# UBC-Thunderbots_PCB_Power__archive_power.net
KiCad netlist of a schematic drawn in Altium Designer
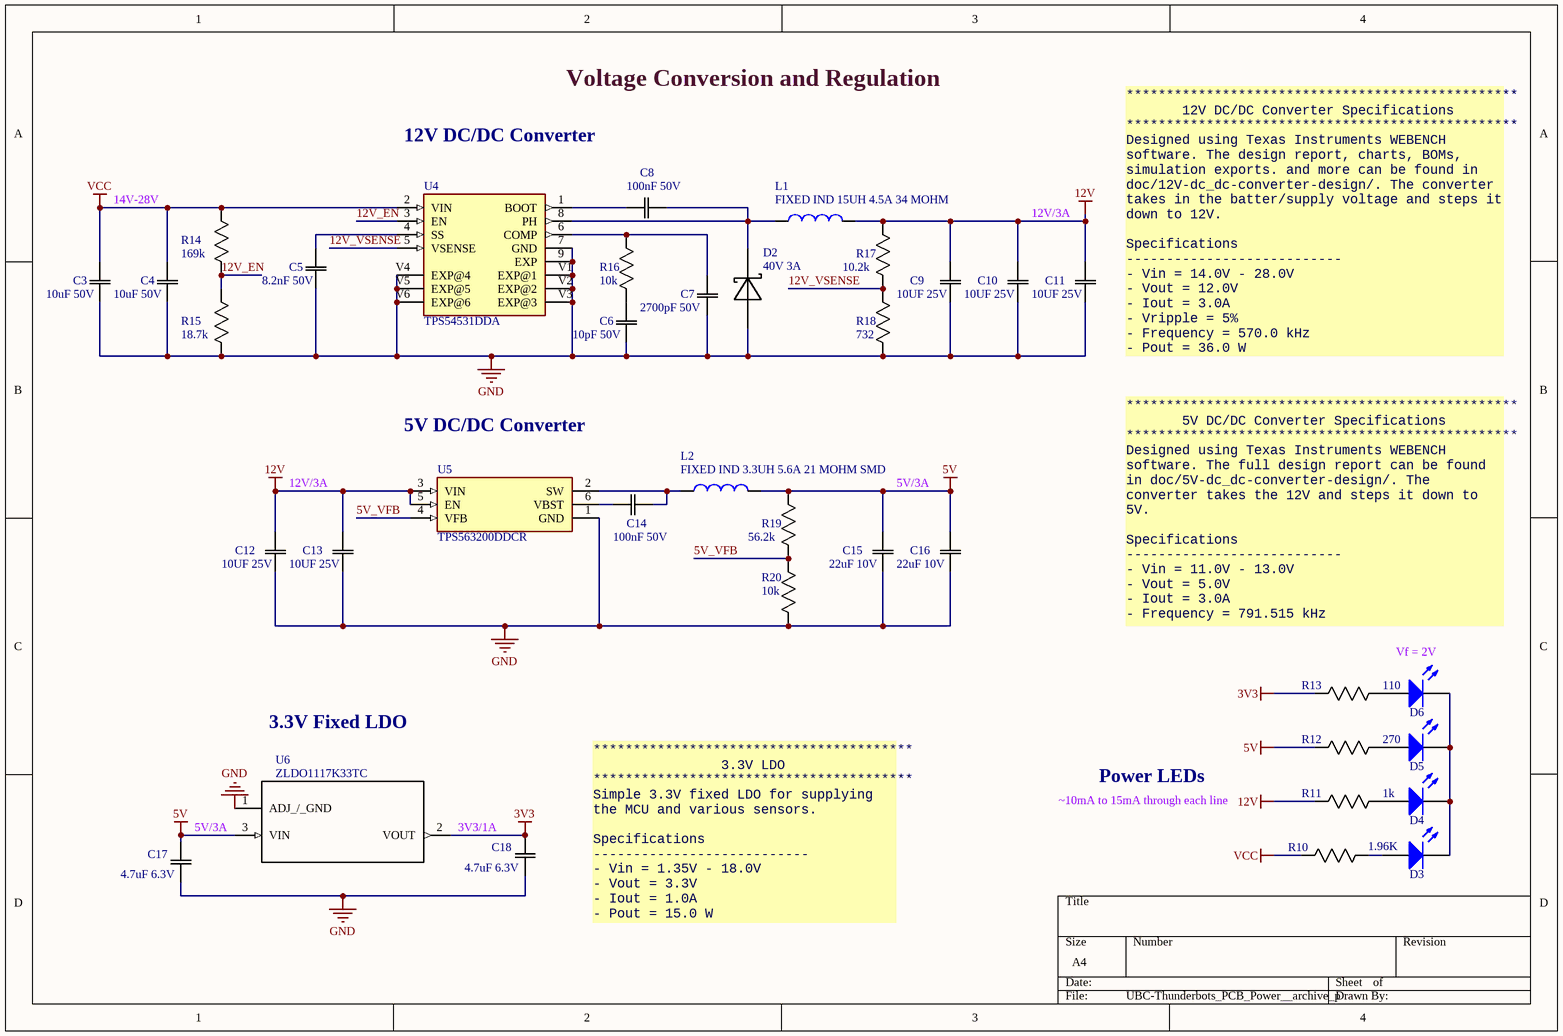
[diagram p0: UBC-Thunderbots_PCB_Power__archive_power-v2.2_pcb__regulation.SchDoc]

(export (version "E")
  (design (tool "Eeschema 10.0.6"))
  (components
    (comp (ref "C3")
      (value "10uF 50V")
      (footprint "1210")
      (description "CAP CER 10UF 50V X7R")
      (fields (field (name "TOLERANCE") "10%"))
      (libsource (lib "AltiumLibraries") (part "CAP 10uF 50V"))
    )
    (comp (ref "C4")
      (value "10uF 50V")
      (footprint "1210")
      (description "CAP CER 10UF 50V X7R")
      (fields (field (name "TOLERANCE") "10%"))
      (libsource (lib "AltiumLibraries") (part "CAP 10uF 50V"))
    )
    (comp (ref "C5")
      (value "8.2nF 50V")
      (footprint "0805")
      (description "CAP CER 8200PF 50V X7R 0805")
      (fields (field (name "TOLERANCE") "10%"))
      (libsource (lib "AltiumLibraries") (part "CAP 8.2nF 50V"))
    )
    (comp (ref "C6")
      (value "10pF 50V")
      (footprint "0603")
      (description "CAP CER 10PF 50V X7R 0603")
      (fields (field (name "TOLERANCE") "10%"))
      (libsource (lib "AltiumLibraries") (part "CAP 10pF 50V"))
    )
    (comp (ref "C7")
      (value "2700pF 50V")
      (footprint "0805")
      (description "CAP CER 2700PF 50V X7R 0805")
      (fields (field (name "TOLERANCE") "10%"))
      (libsource (lib "AltiumLibraries") (part "CAP 2700pF 50V"))
    )
    (comp (ref "C8")
      (value "100nF 50V")
      (footprint "0805")
      (description "CAP CER 0.1UF 50V X7R 0805")
      (fields (field (name "TOLERANCE") "10%"))
      (libsource (lib "AltiumLibraries") (part "CAP 100nF 50V"))
    )
    (comp (ref "C9")
      (value "10UF 25V")
      (footprint "1206")
      (description "CAP CER 10UF 25V X5R 1206")
      (fields (field (name "TOLERANCE") "10%"))
      (libsource (lib "AltiumLibraries") (part "CAP 10uF 25V"))
    )
    (comp (ref "C10")
      (value "10UF 25V")
      (footprint "1206")
      (description "CAP CER 10UF 25V X5R 1206")
      (fields (field (name "TOLERANCE") "10%"))
      (libsource (lib "AltiumLibraries") (part "CAP 10uF 25V"))
    )
    (comp (ref "C11")
      (value "10UF 25V")
      (footprint "1206")
      (description "CAP CER 10UF 25V X5R 1206")
      (fields (field (name "TOLERANCE") "10%"))
      (libsource (lib "AltiumLibraries") (part "CAP 10uF 25V"))
    )
    (comp (ref "C12")
      (value "10UF 25V")
      (footprint "1206")
      (description "CAP CER 10UF 25V X5R 1206")
      (fields (field (name "TOLERANCE") "10%"))
      (libsource (lib "AltiumLibraries") (part "CAP 10uF 25V"))
    )
    (comp (ref "C13")
      (value "10UF 25V")
      (footprint "1206")
      (description "CAP CER 10UF 25V X5R 1206")
      (fields (field (name "TOLERANCE") "10%"))
      (libsource (lib "AltiumLibraries") (part "CAP 10uF 25V"))
    )
    (comp (ref "C14")
      (value "100nF 50V")
      (footprint "0805")
      (description "CAP CER 0.1UF 50V X7R 0805")
      (fields (field (name "TOLERANCE") "10%"))
      (libsource (lib "AltiumLibraries") (part "CAP 100nF 50V"))
    )
    (comp (ref "C15")
      (value "22uF 10V")
      (footprint "0805")
      (description "CAP CER 2.2UF 10V X5R 0805")
      (fields (field (name "TOLERANCE") "20%"))
      (libsource (lib "AltiumLibraries") (part "CAP 22uF 10V"))
    )
    (comp (ref "C16")
      (value "22uF 10V")
      (footprint "0805")
      (description "CAP CER 2.2UF 10V X5R 0805")
      (fields (field (name "TOLERANCE") "20%"))
      (libsource (lib "AltiumLibraries") (part "CAP 22uF 10V"))
    )
    (comp (ref "C17")
      (value "4.7uF 6.3V")
      (footprint "0805")
      (description "CAP CER 4.7UF 6.3V X5R 0805")
      (fields (field (name "TOLERANCE") "10%"))
      (libsource (lib "AltiumLibraries") (part "CAP 4.7uF 6.3V"))
    )
    (comp (ref "C18")
      (value "4.7uF 6.3V")
      (footprint "0805")
      (description "CAP CER 4.7UF 6.3V X5R 0805")
      (fields (field (name "TOLERANCE") "10%"))
      (libsource (lib "AltiumLibraries") (part "CAP 4.7uF 6.3V"))
    )
    (comp (ref "D2")
      (value "40V 3A")
      (footprint "DO-214AC")
      (description "Diode Schottky 40V 3A Surface Mount SMA")
      (libsource (lib "AltiumLibraries") (part "DIODE SCHOTTKY 40V 3A"))
    )
    (comp (ref "D3")
      (value "LED2")
      (footprint "3.2X1.6X1.1")
      (description "Typical RED, GREEN, YELLOW, AMBER GaAs LED")
      (libsource (lib "AltiumLibraries") (part "LED GREEN SMD"))
    )
    (comp (ref "D4")
      (value "LED2")
      (footprint "3.2X1.6X1.1")
      (description "Typical RED, GREEN, YELLOW, AMBER GaAs LED")
      (libsource (lib "AltiumLibraries") (part "LED GREEN SMD"))
    )
    (comp (ref "D5")
      (value "LED2")
      (footprint "3.2X1.6X1.1")
      (description "Typical RED, GREEN, YELLOW, AMBER GaAs LED")
      (libsource (lib "AltiumLibraries") (part "LED GREEN SMD"))
    )
    (comp (ref "D6")
      (value "LED2")
      (footprint "3.2X1.6X1.1")
      (description "Typical RED, GREEN, YELLOW, AMBER GaAs LED")
      (libsource (lib "AltiumLibraries") (part "LED GREEN SMD"))
    )
    (comp (ref "L1")
      (value "FIXED IND 15UH 4.5A 34 MOHM")
      (description "15µH Unshielded Wirewound Inductor 4.5A 34mOhm Max Nonstandard")
      (fields (field (name "MP") "SDR1307-150ML") (field (name "MF") "Bourns Inc."))
      (libsource (lib "AltiumLibraries") (part "SDR1307-150ML"))
    )
    (comp (ref "L2")
      (value "FIXED IND 3.3UH 5.6A 21 MOHM SMD")
      (description "3.3µH Semi-Shielded Wirewound Inductor 5.6A 21mOhm Max Nonstandard")
      (fields (field (name "MP") "SRN8040-3R3Y") (field (name "MF") "Bourns Inc."))
      (libsource (lib "AltiumLibraries") (part "SRN8040-3R3Y"))
    )
    (comp (ref "R10")
      (value "1.96K")
      (footprint "0805")
      (description "RES SMD 1.96K OHM 1% 1/8W 0805")
      (fields (field (name "TOLERANCE") "1%"))
      (libsource (lib "AltiumLibraries") (part "RES 1.96k 1/8W"))
    )
    (comp (ref "R11")
      (value "1k")
      (footprint "0805")
      (description "RES SMD 1K OHM 5% 1/8W 0805")
      (fields (field (name "TOLERANCE") "5%"))
      (libsource (lib "AltiumLibraries") (part "RES 1k 1/8W"))
    )
    (comp (ref "R12")
      (value "270")
      (footprint "0805")
      (description "RES SMD 270 OHM 5% 1/8W 0805")
      (fields (field (name "TOLERANCE") "5%"))
      (libsource (lib "AltiumLibraries") (part "RES 270 1/8W"))
    )
    (comp (ref "R13")
      (value "110")
      (footprint "0805")
      (description "RES SMD 110 OHM 1% 1/8W 0805")
      (fields (field (name "TOLERANCE") "1%"))
      (libsource (lib "AltiumLibraries") (part "RES 110 1/8W"))
    )
    (comp (ref "R14")
      (value "169k")
      (footprint "0805")
      (description "RES SMD 169K OHM 1% 1/8W 0805")
      (fields (field (name "TOLERANCE") "1%"))
      (libsource (lib "AltiumLibraries") (part "RES 169k 1/8W"))
    )
    (comp (ref "R15")
      (value "18.7k")
      (footprint "1206")
      (description "RES SMD 18.7K OHM 1% 1/8W")
      (fields (field (name "TOLERANCE") "1%"))
      (libsource (lib "AltiumLibraries") (part "RES 18.7K OHM 1/8W"))
    )
    (comp (ref "R16")
      (value "10k")
      (footprint "0805")
      (description "RES SMD 10K OHM 1% 1/8W 0805")
      (fields (field (name "TOLERANCE") "1%"))
      (libsource (lib "AltiumLibraries") (part "RES 10k 1/8W"))
    )
    (comp (ref "R17")
      (value "10.2k")
      (footprint "0805")
      (description "RES SMD 10.2K OHM 1% 1/8W 0805")
      (fields (field (name "TOLERANCE") "1%"))
      (libsource (lib "AltiumLibraries") (part "RES 10.2k 1/8W"))
    )
    (comp (ref "R18")
      (value "732")
      (footprint "0805")
      (description "RES SMD 732 OHM 1% 1/8W 0805")
      (fields (field (name "TOLERANCE") "1%"))
      (libsource (lib "AltiumLibraries") (part "RES 732 1/8W"))
    )
    (comp (ref "R19")
      (value "56.2k")
      (footprint "0603")
      (description "RES SMD 56.2K OHM 1% 1/10W 0603")
      (fields (field (name "TOLERANCE") "1%"))
      (libsource (lib "AltiumLibraries") (part "RES 56.2k 1/10W"))
    )
    (comp (ref "R20")
      (value "10k")
      (footprint "0805")
      (description "RES SMD 10K OHM 1% 1/8W 0805")
      (fields (field (name "TOLERANCE") "1%"))
      (libsource (lib "AltiumLibraries") (part "RES 10k 1/8W"))
    )
    (comp (ref "U4")
      (value "TPS54531DDA")
      (footprint "8-PowerSOIC")
      (description "Buck Switching Regulator IC Positive Adjustable 0.8V 1 Output 5A 8-PowerSOIC _0.154, 3.90mm Width_")
      (fields (field (name "MF") "Texas Instruments"))
      (libsource (lib "AltiumLibraries") (part "TPS54531DDA"))
    )
    (comp (ref "U5")
      (value "TPS563200DDCR")
      (footprint "TSOT-23-6")
      (description "Buck Switching Regulator IC Positive Adjustable 0.76V 1 Output 3A SOT-23-6 Thin, TSOT-23-6")
      (fields (field (name "MF") "Texas Instruments"))
      (libsource (lib "AltiumLibraries") (part "TPS563200DDCR"))
    )
    (comp (ref "U6")
      (value "ZLDO1117K33TC")
      (footprint "TO-252-3")
      (description "Linear Voltage Regulator IC Positive Fixed 1 Output  1A TO-252-3")
      (fields (field (name "MF") "Diodes Incorporated"))
      (libsource (lib "AltiumLibraries") (part "ZLDO1117K33TC"))
    )
  )
  (nets
    (net (code "1") (name "/5V_VFB") (class "Default")
      (node (ref "R19") (pin "2") (pinfunction "R2_2") (pintype "passive"))
      (node (ref "R20") (pin "2") (pinfunction "R2_2") (pintype "passive"))
      (node (ref "U5") (pin "4") (pinfunction "VFB_4") (pintype "input"))
    )
    (net (code "2") (name "/12V_EN") (class "Default")
      (node (ref "R14") (pin "2") (pinfunction "R2_2") (pintype "passive"))
      (node (ref "R15") (pin "1") (pinfunction "R1_1") (pintype "passive"))
      (node (ref "U4") (pin "3") (pinfunction "EN_3") (pintype "input"))
    )
    (net (code "3") (name "/12V_VSENSE") (class "Default")
      (node (ref "R17") (pin "1") (pinfunction "R1_1") (pintype "passive"))
      (node (ref "R18") (pin "2") (pinfunction "R2_2") (pintype "passive"))
      (node (ref "U4") (pin "5") (pinfunction "VSENSE_5") (pintype "input"))
    )
    (net (code "4") (name "3V3") (class "Default")
      (node (ref "C18") (pin "1") (pinfunction "C1_1") (pintype "passive"))
      (node (ref "R13") (pin "1") (pinfunction "R1_1") (pintype "passive"))
      (node (ref "U6") (pin "2") (pinfunction "VOUT_2") (pintype "output"))
    )
    (net (code "5") (name "5V") (class "Default")
      (node (ref "C15") (pin "2") (pinfunction "C2_2") (pintype "passive"))
      (node (ref "C16") (pin "2") (pinfunction "C2_2") (pintype "passive"))
      (node (ref "C17") (pin "1") (pinfunction "C1_1") (pintype "passive"))
      (node (ref "L2") (pin "2") (pinfunction "2_2") (pintype "passive"))
      (node (ref "R12") (pin "1") (pinfunction "R1_1") (pintype "passive"))
      (node (ref "R19") (pin "1") (pinfunction "R1_1") (pintype "passive"))
      (node (ref "U6") (pin "3") (pinfunction "VIN_3") (pintype "input"))
    )
    (net (code "6") (name "12V") (class "Default")
      (node (ref "C10") (pin "2") (pinfunction "C2_2") (pintype "passive"))
      (node (ref "C11") (pin "2") (pinfunction "C2_2") (pintype "passive"))
      (node (ref "C12") (pin "2") (pinfunction "C2_2") (pintype "passive"))
      (node (ref "C13") (pin "2") (pinfunction "C2_2") (pintype "passive"))
      (node (ref "C9") (pin "2") (pinfunction "C2_2") (pintype "passive"))
      (node (ref "L1") (pin "2") (pinfunction "2_2") (pintype "passive"))
      (node (ref "R11") (pin "1") (pinfunction "R1_1") (pintype "passive"))
      (node (ref "R17") (pin "2") (pinfunction "R2_2") (pintype "passive"))
      (node (ref "U5") (pin "3") (pinfunction "VIN_3") (pintype "input"))
      (node (ref "U5") (pin "5") (pinfunction "EN_5") (pintype "input"))
    )
    (net (code "7") (name "GND") (class "Default")
      (node (ref "C10") (pin "1") (pinfunction "C1_1") (pintype "passive"))
      (node (ref "C11") (pin "1") (pinfunction "C1_1") (pintype "passive"))
      (node (ref "C12") (pin "1") (pinfunction "C1_1") (pintype "passive"))
      (node (ref "C13") (pin "1") (pinfunction "C1_1") (pintype "passive"))
      (node (ref "C15") (pin "1") (pinfunction "C1_1") (pintype "passive"))
      (node (ref "C16") (pin "1") (pinfunction "C1_1") (pintype "passive"))
      (node (ref "C17") (pin "2") (pinfunction "C2_2") (pintype "passive"))
      (node (ref "C18") (pin "2") (pinfunction "C2_2") (pintype "passive"))
      (node (ref "C3") (pin "1") (pinfunction "C1_1") (pintype "passive"))
      (node (ref "C4") (pin "1") (pinfunction "C1_1") (pintype "passive"))
      (node (ref "C5") (pin "1") (pinfunction "C1_1") (pintype "passive"))
      (node (ref "C6") (pin "1") (pinfunction "C1_1") (pintype "passive"))
      (node (ref "C7") (pin "1") (pinfunction "C1_1") (pintype "passive"))
      (node (ref "C9") (pin "1") (pinfunction "C1_1") (pintype "passive"))
      (node (ref "D2") (pin "A") (pinfunction "A_A") (pintype "passive"))
      (node (ref "R15") (pin "2") (pinfunction "R2_2") (pintype "passive"))
      (node (ref "R18") (pin "1") (pinfunction "R1_1") (pintype "passive"))
      (node (ref "R20") (pin "1") (pinfunction "R1_1") (pintype "passive"))
      (node (ref "U4") (pin "7") (pinfunction "GND_7") (pintype "power_in"))
      (node (ref "U4") (pin "9") (pinfunction "EXP_9") (pintype "power_in"))
      (node (ref "U4") (pin "V1") (pinfunction "EXP@1_V1") (pintype "power_in"))
      (node (ref "U4") (pin "V2") (pinfunction "EXP@2_V2") (pintype "power_in"))
      (node (ref "U4") (pin "V3") (pinfunction "EXP@3_V3") (pintype "power_in"))
      (node (ref "U4") (pin "V4") (pinfunction "EXP@4_V4") (pintype "power_in"))
      (node (ref "U4") (pin "V5") (pinfunction "EXP@5_V5") (pintype "power_in"))
      (node (ref "U4") (pin "V6") (pinfunction "EXP@6_V6") (pintype "power_in"))
      (node (ref "U5") (pin "1") (pinfunction "GND_1") (pintype "power_in"))
      (node (ref "U6") (pin "1") (pinfunction "ADJ_/_GND_1") (pintype "power_in"))
    )
    (net (code "8") (name "Net-(C5-C2)") (class "Default")
      (node (ref "C5") (pin "2") (pinfunction "C2_2") (pintype "passive"))
      (node (ref "U4") (pin "4") (pinfunction "SS_4") (pintype "input"))
    )
    (net (code "9") (name "Net-(C6-C2)") (class "Default")
      (node (ref "C6") (pin "2") (pinfunction "C2_2") (pintype "passive"))
      (node (ref "R16") (pin "2") (pinfunction "R2_2") (pintype "passive"))
    )
    (net (code "10") (name "Net-(C7-C2)") (class "Default")
      (node (ref "C7") (pin "2") (pinfunction "C2_2") (pintype "passive"))
      (node (ref "R16") (pin "1") (pinfunction "R1_1") (pintype "passive"))
      (node (ref "U4") (pin "6") (pinfunction "COMP_6") (pintype "output"))
    )
    (net (code "11") (name "Net-(C8-C1)") (class "Default")
      (node (ref "C8") (pin "1") (pinfunction "C1_1") (pintype "passive"))
      (node (ref "U4") (pin "1") (pinfunction "BOOT_1") (pintype "output"))
    )
    (net (code "12") (name "Net-(C8-C2)") (class "Default")
      (node (ref "C8") (pin "2") (pinfunction "C2_2") (pintype "passive"))
      (node (ref "D2") (pin "C") (pinfunction "K_C") (pintype "passive"))
      (node (ref "L1") (pin "1") (pinfunction "1_1") (pintype "passive"))
      (node (ref "U4") (pin "8") (pinfunction "PH_8") (pintype "output"))
    )
    (net (code "13") (name "Net-(C14-C1)") (class "Default")
      (node (ref "C14") (pin "1") (pinfunction "C1_1") (pintype "passive"))
      (node (ref "U5") (pin "6") (pinfunction "VBST_6") (pintype "passive"))
    )
    (net (code "14") (name "Net-(C14-C2)") (class "Default")
      (node (ref "C14") (pin "2") (pinfunction "C2_2") (pintype "passive"))
      (node (ref "L2") (pin "1") (pinfunction "1_1") (pintype "passive"))
      (node (ref "U5") (pin "2") (pinfunction "SW_2") (pintype "passive"))
    )
    (net (code "15") (name "Net-(D3-A)") (class "Default")
      (node (ref "D3") (pin "1") (pinfunction "A_1") (pintype "passive"))
      (node (ref "R10") (pin "2") (pinfunction "R2_2") (pintype "passive"))
    )
    (net (code "16") (name "Net-(D3-K)") (class "Default")
      (node (ref "D3") (pin "2") (pinfunction "K_2") (pintype "passive"))
      (node (ref "D4") (pin "2") (pinfunction "K_2") (pintype "passive"))
      (node (ref "D5") (pin "2") (pinfunction "K_2") (pintype "passive"))
      (node (ref "D6") (pin "2") (pinfunction "K_2") (pintype "passive"))
    )
    (net (code "17") (name "Net-(D4-A)") (class "Default")
      (node (ref "D4") (pin "1") (pinfunction "A_1") (pintype "passive"))
      (node (ref "R11") (pin "2") (pinfunction "R2_2") (pintype "passive"))
    )
    (net (code "18") (name "Net-(D5-A)") (class "Default")
      (node (ref "D5") (pin "1") (pinfunction "A_1") (pintype "passive"))
      (node (ref "R12") (pin "2") (pinfunction "R2_2") (pintype "passive"))
    )
    (net (code "19") (name "Net-(D6-A)") (class "Default")
      (node (ref "D6") (pin "1") (pinfunction "A_1") (pintype "passive"))
      (node (ref "R13") (pin "2") (pinfunction "R2_2") (pintype "passive"))
    )
    (net (code "20") (name "VCC") (class "Default")
      (node (ref "C3") (pin "2") (pinfunction "C2_2") (pintype "passive"))
      (node (ref "C4") (pin "2") (pinfunction "C2_2") (pintype "passive"))
      (node (ref "R10") (pin "1") (pinfunction "R1_1") (pintype "passive"))
      (node (ref "R14") (pin "1") (pinfunction "R1_1") (pintype "passive"))
      (node (ref "U4") (pin "2") (pinfunction "VIN_2") (pintype "input"))
    )
  )
)
